# POWER.net
KiCad netlist of a schematic drawn in Altium Designer
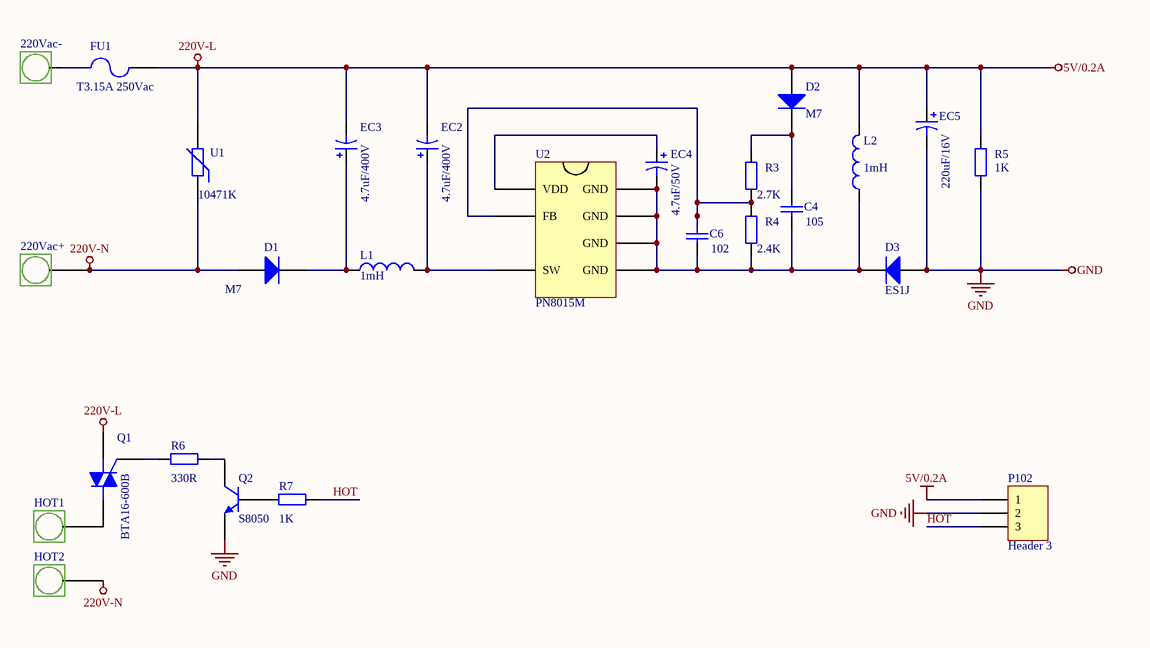
[diagram p0: POWER.SchDoc]

(export (version "E")
  (design (tool "Eeschema 10.0.6"))
  (components
    (comp (ref "220Vac+") (value "焊接点") (footprint "HanJie") (libsource (lib "HT_SHUIHU") (part "PORT")))
    (comp (ref "220Vac-") (value "焊接点") (footprint "HanJie") (libsource (lib "HT_SHUIHU") (part "PORT")))
    (comp (ref "C4")
      (value "105")
      (footprint "6-0805_N")
      (description "Capacitor")
      (fields (field (name "Comment") "电容") (field (name "PUBLISHER") "Altium Limited"))
      (libsource (lib "Miscellaneous Devices") (part "Cap"))
    )
    (comp (ref "C6")
      (value "102")
      (footprint "6-0805_N")
      (description "Capacitor")
      (fields (field (name "Comment") "电容") (field (name "PUBLISHER") "Altium Limited"))
      (libsource (lib "Miscellaneous Devices") (part "Cap"))
    )
    (comp (ref "D1")
      (value "M7")
      (footprint "ErJiGuan-M7")
      (description "1 Amp General Purpose Rectifier")
      (fields (field (name "PUBLISHER") "Altium Limited"))
      (libsource (lib "Miscellaneous Devices") (part "Diode 1N4001"))
    )
    (comp (ref "D2")
      (value "M7")
      (footprint "ErJiGuan-M7")
      (description "1 Amp General Purpose Rectifier")
      (fields (field (name "PUBLISHER") "Altium Limited"))
      (libsource (lib "Miscellaneous Devices") (part "Diode 1N4007"))
    )
    (comp (ref "D3")
      (value "ES1J")
      (footprint "ErJiGuan-M7")
      (description "Default Diode")
      (fields (field (name "PUBLISHER") "Altium Limited"))
      (libsource (lib "Miscellaneous Devices") (part "Diode"))
    )
    (comp (ref "EC2")
      (value "4.7uF/400V")
      (footprint "DianRong-3.5mm")
      (description "Polarized Capacitor (Radial)")
      (fields (field (name "Comment") "电容") (field (name "PUBLISHER") "Altium Limited"))
      (libsource (lib "Miscellaneous Devices") (part "Cap Pol1"))
    )
    (comp (ref "EC3")
      (value "4.7uF/400V")
      (footprint "DianRong-3.5mm")
      (description "Polarized Capacitor (Radial)")
      (fields (field (name "Comment") "电容") (field (name "PUBLISHER") "Altium Limited"))
      (libsource (lib "Miscellaneous Devices") (part "Cap Pol1"))
    )
    (comp (ref "EC4")
      (value "4.7uF/50V")
      (footprint "DianRong-3.3mm")
      (description "Polarized Capacitor (Radial)")
      (fields (field (name "Comment") "电容") (field (name "PUBLISHER") "Altium Limited"))
      (libsource (lib "Miscellaneous Devices") (part "Cap Pol1"))
    )
    (comp (ref "EC5")
      (value "220uF/16V")
      (footprint "DianRong-3.2mm")
      (description "Polarized Capacitor (Radial)")
      (fields (field (name "Comment") "电容") (field (name "PUBLISHER") "Altium Limited"))
      (libsource (lib "Miscellaneous Devices") (part "Cap Pol1"))
    )
    (comp (ref "FU1")
      (value "T3.15A 250Vac")
      (footprint "BaoXianSi")
      (description "Fuse")
      (fields (field (name "PUBLISHER") "Altium Limited"))
      (libsource (lib "Miscellaneous Devices") (part "Fuse 2"))
    )
    (comp (ref "HOT1") (value "焊接点") (footprint "HanJie") (libsource (lib "HT_SHUIHU") (part "PORT")))
    (comp (ref "HOT2") (value "焊接点") (footprint "HanJie") (libsource (lib "HT_SHUIHU") (part "PORT")))
    (comp (ref "L1")
      (value "1mH")
      (footprint "DianGan-12.5mm")
      (description "Inductor")
      (fields (field (name "Comment") "电感") (field (name "PUBLISHER") "Altium Limited"))
      (libsource (lib "Miscellaneous Devices") (part "Inductor"))
    )
    (comp (ref "L2")
      (value "1mH")
      (footprint "DianGan")
      (description "Inductor")
      (fields (field (name "Comment") "电感") (field (name "PUBLISHER") "Altium Limited"))
      (libsource (lib "Miscellaneous Devices") (part "Inductor"))
    )
    (comp (ref "P102")
      (value "Header 3")
      (footprint "HDR1X3")
      (description "Header, 3-Pin")
      (fields (field (name "PUBLISHER") "Altium Limited"))
      (libsource (lib "Miscellaneous Connectors") (part "Header 3"))
    )
    (comp (ref "Q1")
      (value "BTA16-600B")
      (footprint "BTA16-600B")
      (description "Silicon Bidirectional Triode Thyristor")
      (fields (field (name "PUBLISHER") "Altium Limited"))
      (libsource (lib "Miscellaneous Devices") (part "Triac"))
    )
    (comp (ref "Q2")
      (value "S8050")
      (footprint "SOT-23_L")
      (description "NPN Bipolar Transistor")
      (fields (field (name "PUBLISHER") "Altium Limited"))
      (libsource (lib "Miscellaneous Devices") (part "QNPN"))
    )
    (comp (ref "R3")
      (value "2.7K")
      (footprint "6-0805_N")
      (description "Resistor")
      (fields (field (name "Comment") "电阻") (field (name "PUBLISHER") "Altium Limited"))
      (libsource (lib "Miscellaneous Devices") (part "Res2"))
    )
    (comp (ref "R4")
      (value "2.4K")
      (footprint "6-0805_N")
      (description "Resistor")
      (fields (field (name "Comment") "电阻") (field (name "PUBLISHER") "Altium Limited"))
      (libsource (lib "Miscellaneous Devices") (part "Res2"))
    )
    (comp (ref "R5")
      (value "1K")
      (footprint "6-0805_N")
      (description "Resistor")
      (fields (field (name "Comment") "电阻") (field (name "PUBLISHER") "Altium Limited"))
      (libsource (lib "Miscellaneous Devices") (part "Res2"))
    )
    (comp (ref "R6")
      (value "330R")
      (footprint "6-0805_N")
      (description "Resistor")
      (fields (field (name "Comment") "电阻") (field (name "PUBLISHER") "Altium Limited"))
      (libsource (lib "") (part "Res2_1"))
    )
    (comp (ref "R7")
      (value "1K")
      (footprint "6-0805_N")
      (description "Resistor")
      (fields (field (name "Comment") "电阻") (field (name "PUBLISHER") "Altium Limited"))
      (libsource (lib "") (part "Res2_1"))
    )
    (comp (ref "U1")
      (value "10471K")
      (footprint "YaMinDianZhu")
      (description "Varistor (Voltage-Sensitive Resistor)")
      (fields (field (name "PUBLISHER") "Altium Limited"))
      (libsource (lib "Miscellaneous Devices") (part "Res Varistor"))
    )
    (comp (ref "U2")
      (value "PN8015M")
      (footprint "SOP7-PN8015M")
      (libsource (lib "HT_SHUIHU") (part "PN8015"))
    )
  )
  (nets
    (net (code "1") (name "/HOT") (class "Default")
      (node (ref "P102") (pin "3") (pinfunction "3_3") (pintype "passive"))
      (node (ref "R7") (pin "2") (pinfunction "2_2") (pintype "passive"))
    )
    (net (code "2") (name "220V-L") (class "Default")
      (node (ref "D2") (pin "1") (pinfunction "A_1") (pintype "passive"))
      (node (ref "EC2") (pin "2") (pinfunction "2_2") (pintype "passive"))
      (node (ref "EC3") (pin "2") (pinfunction "2_2") (pintype "passive"))
      (node (ref "EC5") (pin "1") (pinfunction "1_1") (pintype "passive"))
      (node (ref "FU1") (pin "2") (pinfunction "2_2") (pintype "passive"))
      (node (ref "L2") (pin "2") (pinfunction "2_2") (pintype "passive"))
      (node (ref "P102") (pin "1") (pinfunction "1_1") (pintype "passive"))
      (node (ref "Q1") (pin "1") (pinfunction "M1_1") (pintype "passive"))
      (node (ref "R5") (pin "2") (pinfunction "2_2") (pintype "passive"))
      (node (ref "U1") (pin "2") (pinfunction "2_2") (pintype "passive"))
    )
    (net (code "3") (name "220V-N") (class "Default")
      (node (ref "220Vac+") (pin "1") (pinfunction "P_1") (pintype "passive"))
      (node (ref "D1") (pin "1") (pinfunction "A_1") (pintype "passive"))
      (node (ref "HOT2") (pin "1") (pinfunction "P_1") (pintype "passive"))
      (node (ref "U1") (pin "1") (pinfunction "1_1") (pintype "passive"))
    )
    (net (code "4") (name "GND") (class "Default")
      (node (ref "D3") (pin "1") (pinfunction "A_1") (pintype "passive"))
      (node (ref "EC5") (pin "2") (pinfunction "2_2") (pintype "passive"))
      (node (ref "P102") (pin "2") (pinfunction "2_2") (pintype "passive"))
      (node (ref "Q2") (pin "2") (pinfunction "E_2") (pintype "passive"))
      (node (ref "R5") (pin "1") (pinfunction "1_1") (pintype "passive"))
    )
    (net (code "5") (name "Net-(220Vac--P)") (class "Default")
      (node (ref "220Vac-") (pin "1") (pinfunction "P_1") (pintype "passive"))
      (node (ref "FU1") (pin "1") (pinfunction "1_1") (pintype "passive"))
    )
    (net (code "6") (name "Net-(D1-K)") (class "Default")
      (node (ref "D1") (pin "2") (pinfunction "K_2") (pintype "passive"))
      (node (ref "EC3") (pin "1") (pinfunction "1_1") (pintype "passive"))
      (node (ref "L1") (pin "1") (pinfunction "1_1") (pintype "passive"))
    )
    (net (code "7") (name "Net-(D2-K)") (class "Default")
      (node (ref "C4") (pin "2") (pinfunction "2_2") (pintype "passive"))
      (node (ref "D2") (pin "2") (pinfunction "K_2") (pintype "passive"))
      (node (ref "R3") (pin "2") (pinfunction "2_2") (pintype "passive"))
    )
    (net (code "8") (name "Net-(D3-K)") (class "Default")
      (node (ref "C4") (pin "1") (pinfunction "1_1") (pintype "passive"))
      (node (ref "C6") (pin "1") (pinfunction "1_1") (pintype "passive"))
      (node (ref "D3") (pin "2") (pinfunction "K_2") (pintype "passive"))
      (node (ref "EC4") (pin "2") (pinfunction "2_2") (pintype "passive"))
      (node (ref "L2") (pin "1") (pinfunction "1_1") (pintype "passive"))
      (node (ref "R4") (pin "1") (pinfunction "1_1") (pintype "passive"))
      (node (ref "U2") (pin "4") (pinfunction "GND_4") (pintype "passive"))
      (node (ref "U2") (pin "5") (pinfunction "GND_5") (pintype "passive"))
      (node (ref "U2") (pin "6") (pinfunction "GND_6") (pintype "passive"))
      (node (ref "U2") (pin "7") (pinfunction "GND_7") (pintype "passive"))
    )
    (net (code "9") (name "Net-(HOT1-P)") (class "Default")
      (node (ref "HOT1") (pin "1") (pinfunction "P_1") (pintype "passive"))
      (node (ref "Q1") (pin "2") (pinfunction "M2_2") (pintype "passive"))
    )
    (net (code "10") (name "Net-(Q1-G)") (class "Default")
      (node (ref "Q1") (pin "3") (pinfunction "G_3") (pintype "passive"))
      (node (ref "R6") (pin "1") (pinfunction "1_1") (pintype "passive"))
    )
    (net (code "11") (name "Net-(Q2-B)") (class "Default")
      (node (ref "Q2") (pin "1") (pinfunction "B_1") (pintype "passive"))
      (node (ref "R7") (pin "1") (pinfunction "1_1") (pintype "passive"))
    )
    (net (code "12") (name "Net-(Q2-C)") (class "Default")
      (node (ref "Q2") (pin "3") (pinfunction "C_3") (pintype "passive"))
      (node (ref "R6") (pin "2") (pinfunction "2_2") (pintype "passive"))
    )
    (net (code "13") (name "Net-(U2-FB)") (class "Default")
      (node (ref "C6") (pin "2") (pinfunction "2_2") (pintype "passive"))
      (node (ref "R3") (pin "1") (pinfunction "1_1") (pintype "passive"))
      (node (ref "R4") (pin "2") (pinfunction "2_2") (pintype "passive"))
      (node (ref "U2") (pin "2") (pinfunction "FB_2") (pintype "passive"))
    )
    (net (code "14") (name "Net-(U2-SW)") (class "Default")
      (node (ref "EC2") (pin "1") (pinfunction "1_1") (pintype "passive"))
      (node (ref "L1") (pin "2") (pinfunction "2_2") (pintype "passive"))
      (node (ref "U2") (pin "3") (pinfunction "SW_3") (pintype "passive"))
    )
    (net (code "15") (name "Net-(U2-VDD)") (class "Default")
      (node (ref "EC4") (pin "1") (pinfunction "1_1") (pintype "passive"))
      (node (ref "U2") (pin "1") (pinfunction "VDD_1") (pintype "passive"))
    )
  )
)
